# Tiny_Programmer_dummy.net
KiCad netlist of a schematic drawn in EAGLE
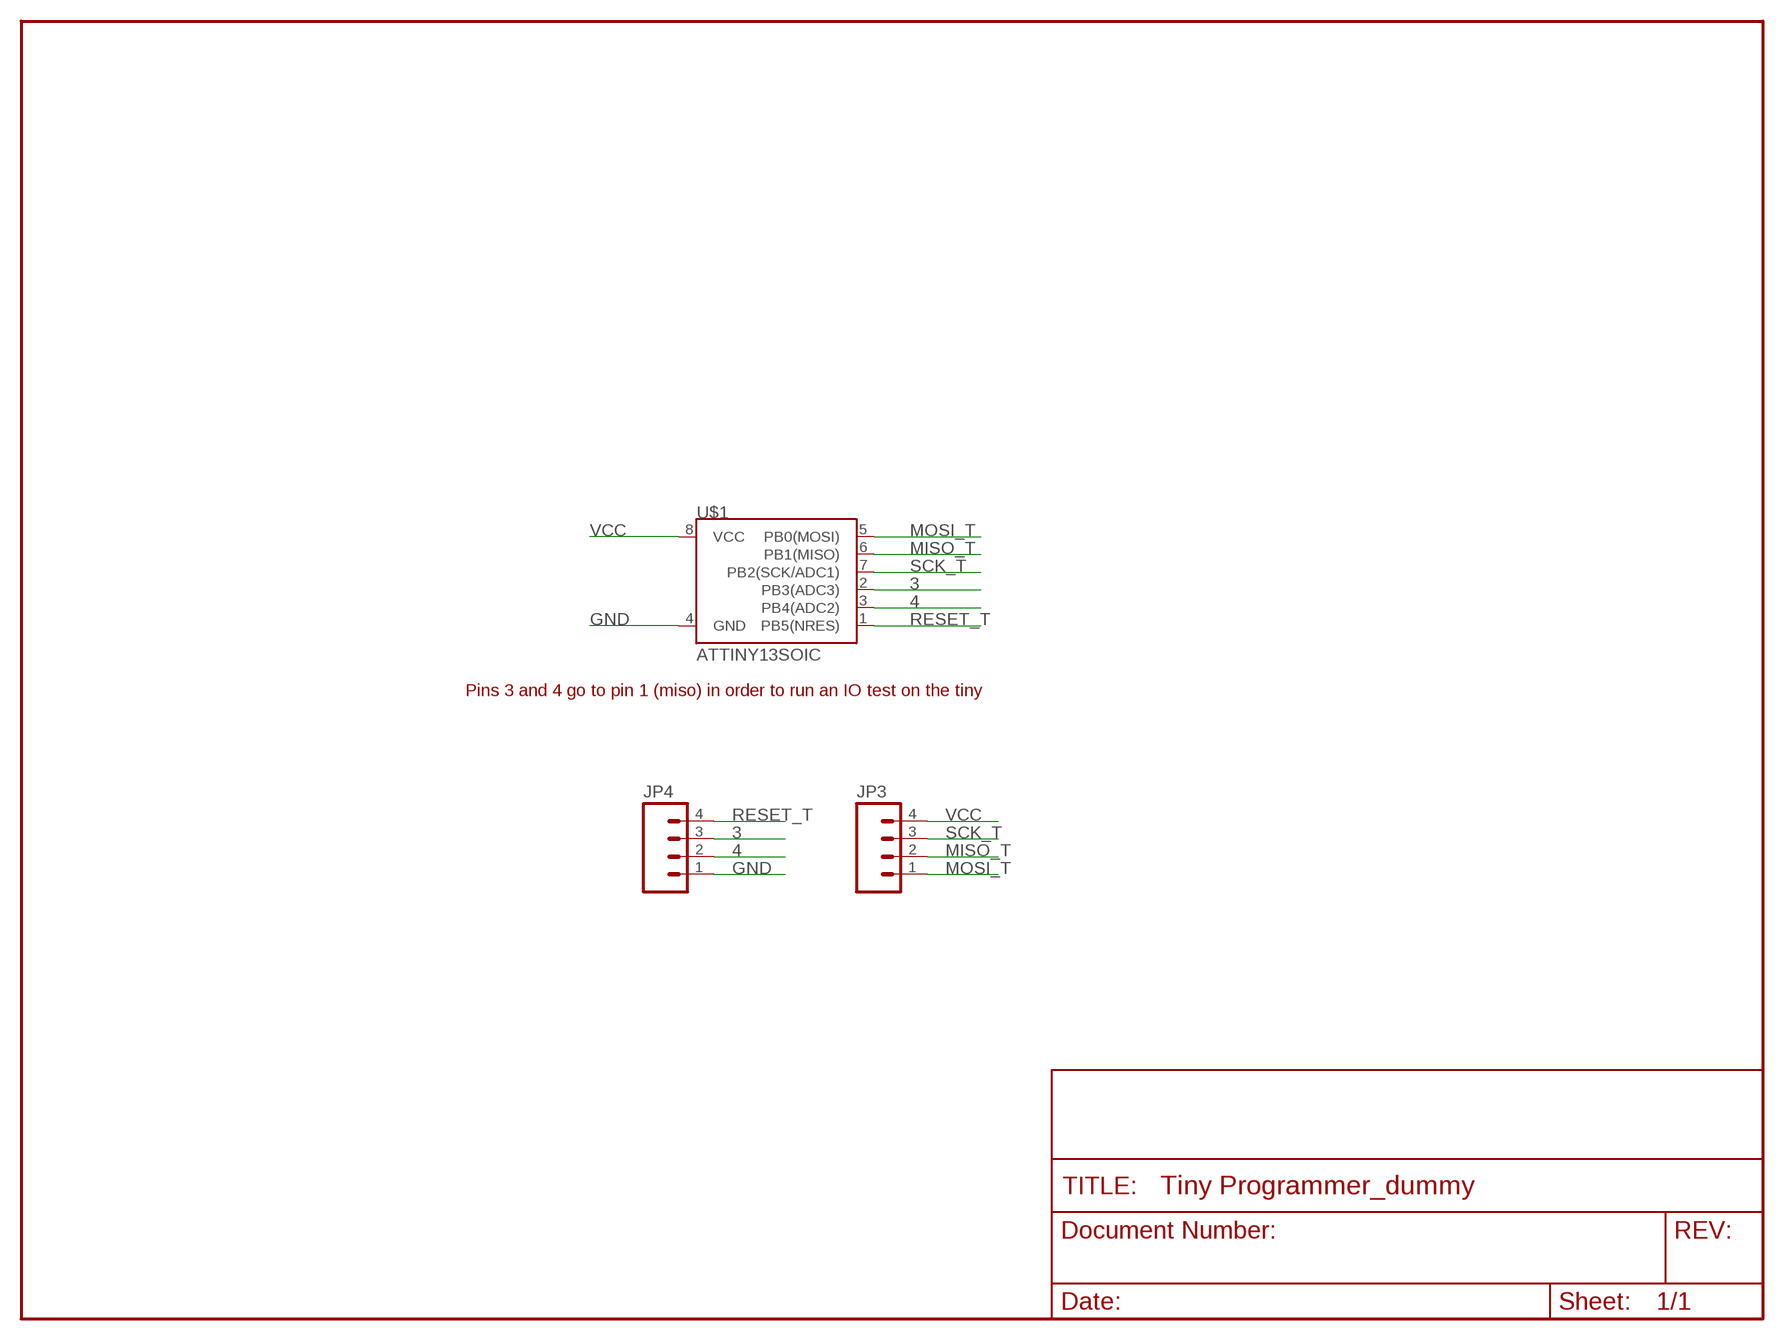
[diagram p0: schematic, sheet 1]

(export (version "E")
  (design (tool "Eeschema 10.0.6"))
  (components
    (comp (ref "JP3")
      (value "M04PTH")
      (footprint "eagle-import:1X04")
      (libsource (lib "eagle-import") (part "M04PTH"))
    )
    (comp (ref "JP4")
      (value "M04PTH")
      (footprint "eagle-import:1X04")
      (libsource (lib "eagle-import") (part "M04PTH"))
    )
    (comp (ref "U$1")
      (value "ATTINY13SOIC")
      (footprint "eagle-import:SO08")
      (libsource (lib "eagle-import") (part "ATTINY13SOIC"))
    )
  )
  (nets
    (net (code "1") (name "/3") (class "Default")
      (node (ref "JP4") (pin "3") (pinfunction "3_3") (pintype "passive"))
      (node (ref "U$1") (pin "2") (pinfunction "PB3(ADC3)_2") (pintype "bidirectional"))
    )
    (net (code "2") (name "/4") (class "Default")
      (node (ref "JP4") (pin "2") (pinfunction "2_2") (pintype "passive"))
      (node (ref "U$1") (pin "3") (pinfunction "PB4(ADC2)_3") (pintype "bidirectional"))
    )
    (net (code "3") (name "/GND") (class "Default")
      (node (ref "JP4") (pin "1") (pinfunction "1_1") (pintype "passive"))
      (node (ref "U$1") (pin "4") (pinfunction "GND_4") (pintype "bidirectional"))
    )
    (net (code "4") (name "/MISO_T") (class "Default")
      (node (ref "JP3") (pin "2") (pinfunction "2_2") (pintype "passive"))
      (node (ref "U$1") (pin "6") (pinfunction "PB1(MISO)_6") (pintype "bidirectional"))
    )
    (net (code "5") (name "/MOSI_T") (class "Default")
      (node (ref "JP3") (pin "1") (pinfunction "1_1") (pintype "passive"))
      (node (ref "U$1") (pin "5") (pinfunction "PB0(MOSI)_5") (pintype "bidirectional"))
    )
    (net (code "6") (name "/RESET_T") (class "Default")
      (node (ref "JP4") (pin "4") (pinfunction "4_4") (pintype "passive"))
      (node (ref "U$1") (pin "1") (pinfunction "PB5(NRES)_1") (pintype "bidirectional"))
    )
    (net (code "7") (name "/SCK_T") (class "Default")
      (node (ref "JP3") (pin "3") (pinfunction "3_3") (pintype "passive"))
      (node (ref "U$1") (pin "7") (pinfunction "PB2(SCK/ADC1)_7") (pintype "bidirectional"))
    )
    (net (code "8") (name "/VCC") (class "Default")
      (node (ref "JP3") (pin "4") (pinfunction "4_4") (pintype "passive"))
      (node (ref "U$1") (pin "8") (pinfunction "VCC_8") (pintype "bidirectional"))
    )
  )
)
